# Sheet1.net
KiCad netlist of a schematic drawn in Altium Designer
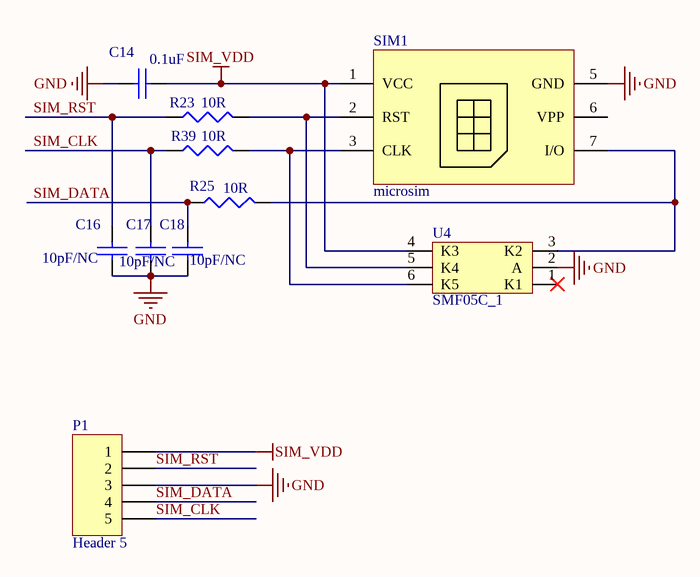
[diagram p0: Sheet1.SchDoc]

(export (version "E")
  (design (tool "Eeschema 10.0.6"))
  (components
    (comp (ref "C14")
      (value "0.1uF")
      (footprint "0402C")
      (description "Capacitor")
      (libsource (lib "ZWLIntegrated_Library") (part "CAP"))
    )
    (comp (ref "C16")
      (value "10pF/NC")
      (footprint "0402C")
      (description "Capacitor")
      (libsource (lib "ZWLIntegrated_Library") (part "CAP"))
    )
    (comp (ref "C17")
      (value "10pF/NC")
      (footprint "0402C")
      (description "Capacitor")
      (libsource (lib "ZWLIntegrated_Library") (part "CAP"))
    )
    (comp (ref "C18")
      (value "10pF/NC")
      (footprint "0402C")
      (description "Capacitor")
      (libsource (lib "ZWLIntegrated_Library") (part "CAP"))
    )
    (comp (ref "P1")
      (value "Header 5")
      (footprint "5×1.25mmSMT")
      (description "Header, 5-Pin")
      (fields (field (name "PUBLISHER") "Altium Limited"))
      (libsource (lib "Miscellaneous Connectors") (part "Header 5"))
    )
    (comp (ref "R23")
      (value "10R")
      (footprint "0402R")
      (libsource (lib "ZWLIntegrated_Library") (part "RES1"))
    )
    (comp (ref "R25")
      (value "10R")
      (footprint "0402R")
      (libsource (lib "ZWLIntegrated_Library") (part "RES1"))
    )
    (comp (ref "R39")
      (value "10R")
      (footprint "0402R")
      (libsource (lib "ZWLIntegrated_Library") (part "RES1"))
    )
    (comp (ref "SIM1")
      (value "microsim")
      (footprint "Nano SIM")
      (libsource (lib "SIM800C 原理图库") (part "microsim"))
    )
    (comp (ref "U4")
      (value "SMF05C_1")
      (footprint "SC70-6L")
      (description "TVS")
      (libsource (lib "SIM800C 原理图库") (part "SMF05C_1"))
    )
  )
  (nets
    (net (code "1") (name "/SIM_CLK") (class "Default")
      (node (ref "C17") (pin "2") (pinfunction "2_2") (pintype "passive"))
      (node (ref "P1") (pin "5") (pinfunction "5_5") (pintype "passive"))
      (node (ref "R39") (pin "1") (pinfunction "1_1") (pintype "passive"))
    )
    (net (code "2") (name "/SIM_DATA") (class "Default")
      (node (ref "C18") (pin "2") (pinfunction "2_2") (pintype "passive"))
      (node (ref "P1") (pin "4") (pinfunction "4_4") (pintype "passive"))
      (node (ref "R25") (pin "1") (pinfunction "1_1") (pintype "passive"))
    )
    (net (code "3") (name "/SIM_RST") (class "Default")
      (node (ref "C16") (pin "2") (pinfunction "2_2") (pintype "passive"))
      (node (ref "P1") (pin "2") (pinfunction "2_2") (pintype "passive"))
      (node (ref "R23") (pin "1") (pinfunction "1_1") (pintype "passive"))
    )
    (net (code "4") (name "GND") (class "Default")
      (node (ref "C14") (pin "1") (pinfunction "1_1") (pintype "passive"))
      (node (ref "C16") (pin "1") (pinfunction "1_1") (pintype "passive"))
      (node (ref "C17") (pin "1") (pinfunction "1_1") (pintype "passive"))
      (node (ref "C18") (pin "1") (pinfunction "1_1") (pintype "passive"))
      (node (ref "P1") (pin "3") (pinfunction "3_3") (pintype "passive"))
      (node (ref "SIM1") (pin "5") (pinfunction "GND_5") (pintype "passive"))
      (node (ref "U4") (pin "2") (pinfunction "A_2") (pintype "passive"))
    )
    (net (code "5") (name "Net-(SIM1-CLK)") (class "Default")
      (node (ref "R39") (pin "2") (pinfunction "2_2") (pintype "passive"))
      (node (ref "SIM1") (pin "3") (pinfunction "CLK_3") (pintype "passive"))
      (node (ref "U4") (pin "6") (pinfunction "K5_6") (pintype "passive"))
    )
    (net (code "6") (name "Net-(SIM1-I{slash}O)") (class "Default")
      (node (ref "R25") (pin "2") (pinfunction "2_2") (pintype "passive"))
      (node (ref "SIM1") (pin "7") (pinfunction "I/O_7") (pintype "passive"))
      (node (ref "U4") (pin "3") (pinfunction "K2_3") (pintype "passive"))
    )
    (net (code "7") (name "Net-(SIM1-RST)") (class "Default")
      (node (ref "R23") (pin "2") (pinfunction "2_2") (pintype "passive"))
      (node (ref "SIM1") (pin "2") (pinfunction "RST_2") (pintype "passive"))
      (node (ref "U4") (pin "5") (pinfunction "K4_5") (pintype "passive"))
    )
    (net (code "8") (name "SIM_VDD") (class "Default")
      (node (ref "C14") (pin "2") (pinfunction "2_2") (pintype "passive"))
      (node (ref "P1") (pin "1") (pinfunction "1_1") (pintype "passive"))
      (node (ref "SIM1") (pin "1") (pinfunction "VCC_1") (pintype "passive"))
      (node (ref "U4") (pin "4") (pinfunction "K3_4") (pintype "passive"))
    )
    (net (code "9") (name "unconnected-(SIM1-VPP-Pad6)") (class "Default")
      (node (ref "SIM1") (pin "6") (pinfunction "VPP_6") (pintype "passive"))
    )
    (net (code "10") (name "unconnected-(U4-K1-Pad1)") (class "Default")
      (node (ref "U4") (pin "1") (pinfunction "K1_1") (pintype "passive+no_connect"))
    )
  )
)
